# SHDN-S10-V00-ShutdownSense.net
KiCad netlist of a schematic drawn in Altium Designer
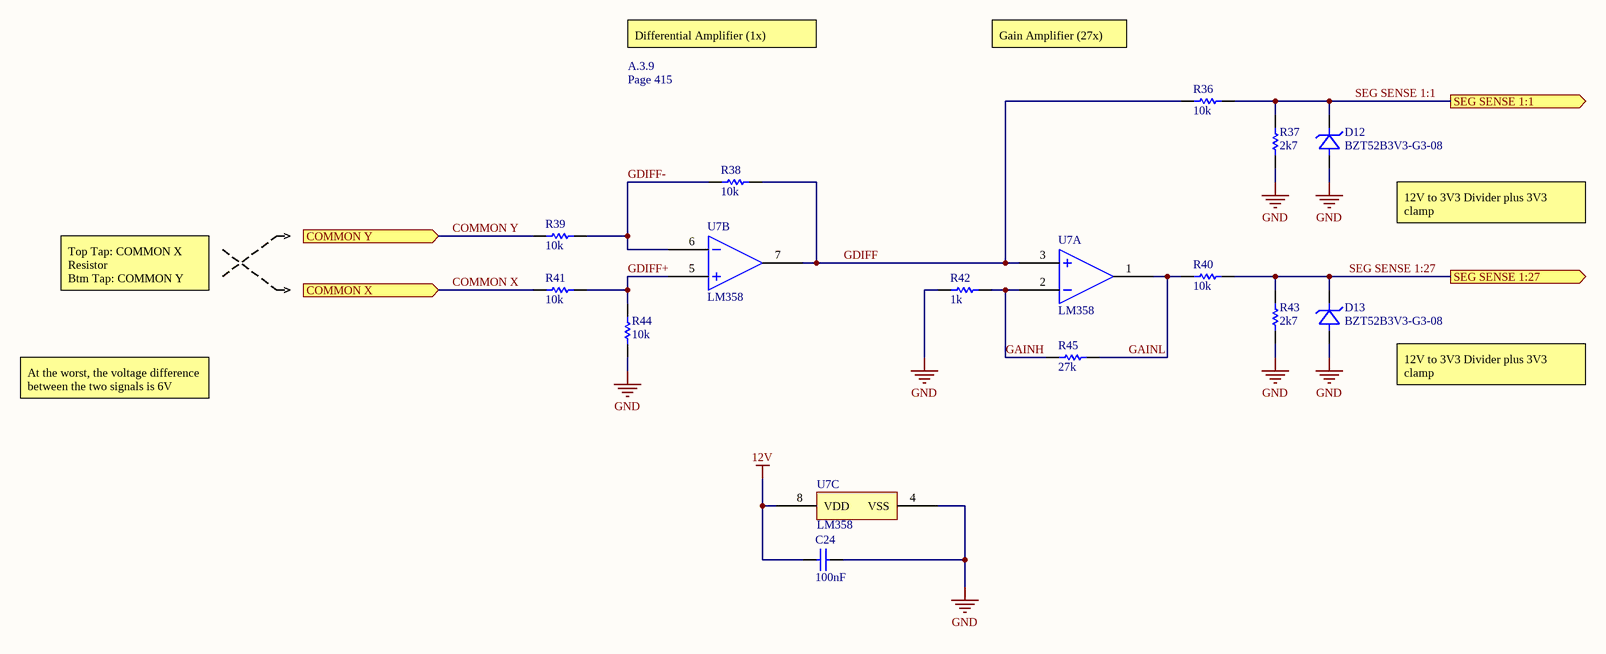
[diagram p0: SHDN-S10-V00-ShutdownSense.SchDoc]

(export (version "E")
  (design (tool "Eeschema 10.0.6"))
  (components
    (comp (ref "C24")
      (value "100nF")
      (footprint "Cap_Ceramic_0603")
      (description "Capacitor, Ceramic, SMD, 100nF, 50V, 5%, X7R, 0603")
      (libsource (lib "StandardCapacitors") (part "100nF 50V 5% X7R 0603"))
    )
    (comp (ref "D12")
      (value "BZT52B3V3-G3-08")
      (footprint "SOD123")
      (description "Diode, SMD, Zenner, 3.3V, 2%, 410mW, SOD-123")
      (libsource (lib "QUTMS_DiodeLibrary") (part "BZT52B3V3-G3-08"))
    )
    (comp (ref "D13")
      (value "BZT52B3V3-G3-08")
      (footprint "SOD123")
      (description "Diode, SMD, Zenner, 3.3V, 2%, 410mW, SOD-123")
      (libsource (lib "QUTMS_DiodeLibrary") (part "BZT52B3V3-G3-08"))
    )
    (comp (ref "R36")
      (value "10k")
      (footprint "Res_ThinFilm_0603")
      (description "Resistor, SMD, 10k, 0.1W, 5%, 0603")
      (libsource (lib "StandardResistors") (part "10k 5% 0603"))
    )
    (comp (ref "R37")
      (value "2k7")
      (footprint "Res_ThinFilm_0603")
      (description "Resistor, SMD, 2k7, 0.1W, 5%, 0603")
      (libsource (lib "StandardResistors") (part "2k7 5% 0603"))
    )
    (comp (ref "R38")
      (value "10k")
      (footprint "Res_ThinFilm_0603")
      (description "Resistor, SMD, 10k, 0.1W, 5%, 0603")
      (libsource (lib "StandardResistors") (part "10k 5% 0603"))
    )
    (comp (ref "R39")
      (value "10k")
      (footprint "Res_ThinFilm_0603")
      (description "Resistor, SMD, 10k, 0.1W, 5%, 0603")
      (libsource (lib "StandardResistors") (part "10k 5% 0603"))
    )
    (comp (ref "R40")
      (value "10k")
      (footprint "Res_ThinFilm_0603")
      (description "Resistor, SMD, 10k, 0.1W, 5%, 0603")
      (libsource (lib "StandardResistors") (part "10k 5% 0603"))
    )
    (comp (ref "R41")
      (value "10k")
      (footprint "Res_ThinFilm_0603")
      (description "Resistor, SMD, 10k, 0.1W, 5%, 0603")
      (libsource (lib "StandardResistors") (part "10k 5% 0603"))
    )
    (comp (ref "R42")
      (value "1k")
      (footprint "Res_ThinFilm_0603")
      (description "Resistor, SMD, 1k, 0.1W, 5%, 0603")
      (libsource (lib "StandardResistors") (part "1k 5% 0603"))
    )
    (comp (ref "R43")
      (value "2k7")
      (footprint "Res_ThinFilm_0603")
      (description "Resistor, SMD, 2k7, 0.1W, 5%, 0603")
      (libsource (lib "StandardResistors") (part "2k7 5% 0603"))
    )
    (comp (ref "R44")
      (value "10k")
      (footprint "Res_ThinFilm_0603")
      (description "Resistor, SMD, 10k, 0.1W, 5%, 0603")
      (libsource (lib "StandardResistors") (part "10k 5% 0603"))
    )
    (comp (ref "R45")
      (value "27k")
      (footprint "Res_ThinFilm_0603")
      (description "Resistor, SMD, 27k, 0.1W, 5%, 0603")
      (libsource (lib "StandardResistors") (part "27k 5% 0603"))
    )
    (comp (ref "U7")
      (value "LM358")
      (footprint "TSSOP-8")
      (description "General Purpose Amplifier 2 Circuit 8-SOIC")
      (libsource (lib "") (part "LM358_1"))
    )
  )
  (nets
    (net (code "1") (name "/COMMON X") (class "Default")
      (node (ref "R41") (pin "1") (pinfunction "1_1") (pintype "passive"))
    )
    (net (code "2") (name "/COMMON Y") (class "Default")
      (node (ref "R39") (pin "1") (pinfunction "1_1") (pintype "passive"))
    )
    (net (code "3") (name "/GAINH") (class "Default")
      (node (ref "R42") (pin "2") (pinfunction "2_2") (pintype "passive"))
      (node (ref "R45") (pin "1") (pinfunction "1_1") (pintype "passive"))
      (node (ref "U7") (pin "2") (pinfunction "IN1-_2") (pintype "passive"))
    )
    (net (code "4") (name "/GAINL") (class "Default")
      (node (ref "R40") (pin "1") (pinfunction "1_1") (pintype "passive"))
      (node (ref "R45") (pin "2") (pinfunction "2_2") (pintype "passive"))
      (node (ref "U7") (pin "1") (pinfunction "OUT1_1") (pintype "passive"))
    )
    (net (code "5") (name "/GDIFF") (class "Default")
      (node (ref "R36") (pin "1") (pinfunction "1_1") (pintype "passive"))
      (node (ref "R38") (pin "2") (pinfunction "2_2") (pintype "passive"))
      (node (ref "U7") (pin "3") (pinfunction "IN1+_3") (pintype "passive"))
      (node (ref "U7") (pin "7") (pinfunction "OUT1_7") (pintype "passive"))
    )
    (net (code "6") (name "/GDIFF+") (class "Default")
      (node (ref "R41") (pin "2") (pinfunction "2_2") (pintype "passive"))
      (node (ref "R44") (pin "2") (pinfunction "2_2") (pintype "passive"))
      (node (ref "U7") (pin "5") (pinfunction "IN2+_5") (pintype "passive"))
    )
    (net (code "7") (name "/GDIFF-") (class "Default")
      (node (ref "R38") (pin "1") (pinfunction "1_1") (pintype "passive"))
      (node (ref "R39") (pin "2") (pinfunction "2_2") (pintype "passive"))
      (node (ref "U7") (pin "6") (pinfunction "IN2-_6") (pintype "passive"))
    )
    (net (code "8") (name "/SEG SENSE 1:1") (class "Default")
      (node (ref "D12") (pin "K") (pinfunction "Cathode_K") (pintype "passive"))
      (node (ref "R36") (pin "2") (pinfunction "2_2") (pintype "passive"))
      (node (ref "R37") (pin "2") (pinfunction "2_2") (pintype "passive"))
    )
    (net (code "9") (name "/SEG SENSE 1:27") (class "Default")
      (node (ref "D13") (pin "K") (pinfunction "Cathode_K") (pintype "passive"))
      (node (ref "R40") (pin "2") (pinfunction "2_2") (pintype "passive"))
      (node (ref "R43") (pin "2") (pinfunction "2_2") (pintype "passive"))
    )
    (net (code "10") (name "12V") (class "Default")
      (node (ref "C24") (pin "1") (pinfunction "1_1") (pintype "passive"))
      (node (ref "U7") (pin "8") (pinfunction "VDD_8") (pintype "passive"))
    )
    (net (code "11") (name "GND") (class "Default")
      (node (ref "C24") (pin "2") (pinfunction "2_2") (pintype "passive"))
      (node (ref "D12") (pin "A") (pinfunction "Anode_A") (pintype "passive"))
      (node (ref "D13") (pin "A") (pinfunction "Anode_A") (pintype "passive"))
      (node (ref "R37") (pin "1") (pinfunction "1_1") (pintype "passive"))
      (node (ref "R42") (pin "1") (pinfunction "1_1") (pintype "passive"))
      (node (ref "R43") (pin "1") (pinfunction "1_1") (pintype "passive"))
      (node (ref "R44") (pin "1") (pinfunction "1_1") (pintype "passive"))
      (node (ref "U7") (pin "4") (pinfunction "VSS_4") (pintype "passive"))
    )
  )
)
